# mag_encoder_Rev1.net
KiCad netlist of a schematic drawn in EAGLE
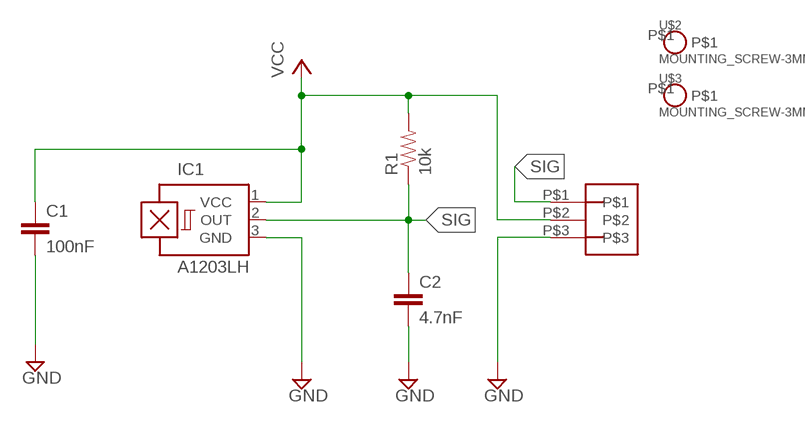
[diagram p0: schematic, sheet 1]

(export (version "E")
  (design (tool "Eeschema 10.0.6"))
  (components
    (comp (ref "C1")
      (value "100nF")
      (footprint "eagle-import:0603-CAP")
      (libsource (lib "eagle-import") (part "CAP0603-CAP"))
    )
    (comp (ref "C2")
      (value "4.7nF")
      (footprint "eagle-import:0603-CAP")
      (libsource (lib "eagle-import") (part "4.7NF-50V-10%(0603)"))
    )
    (comp (ref "IC1")
      (value "A1203LH")
      (footprint "eagle-import:SOT23-W")
      (fields (field (name "MF") "ALLEGRO MICROSYSTEMS, INC.") (field (name "MPN") "A1203LLHLT-T"))
      (libsource (lib "eagle-import") (part "A12?LH03"))
    )
    (comp (ref "R1")
      (value "10k")
      (footprint "eagle-import:0603")
      (libsource (lib "eagle-import") (part "10.5KOHM1/10W1%(0603)"))
    )
    (comp (ref "U$1")
      (value "3_PIN_JST-XH")
      (footprint "eagle-import:3_PIN_JST-XH")
      (libsource (lib "eagle-import") (part "3_PIN_JST-XH"))
    )
    (comp (ref "U$2")
      (value "MOUNTING_SCREW-3MM")
      (footprint "eagle-import:MOUNTING_SCREW-3MM")
      (libsource (lib "eagle-import") (part "MOUNTING_SCREW-3MM"))
    )
    (comp (ref "U$3")
      (value "MOUNTING_SCREW-3MM")
      (footprint "eagle-import:MOUNTING_SCREW-3MM")
      (libsource (lib "eagle-import") (part "MOUNTING_SCREW-3MM"))
    )
  )
  (nets
    (net (code "1") (name "GND") (class "Default")
      (node (ref "C1") (pin "2") (pinfunction "2_2") (pintype "passive"))
      (node (ref "C2") (pin "2") (pinfunction "2_2") (pintype "passive"))
      (node (ref "IC1") (pin "3") (pinfunction "GND_3") (pintype "power_in"))
      (node (ref "U$1") (pin "P$3") (pinfunction "P$3_P$3") (pintype "bidirectional"))
    )
    (net (code "2") (name "SIG") (class "Default")
      (node (ref "C2") (pin "1") (pinfunction "1_1") (pintype "passive"))
      (node (ref "IC1") (pin "2") (pinfunction "OUT_2") (pintype "output"))
      (node (ref "R1") (pin "1") (pinfunction "1_1") (pintype "passive"))
      (node (ref "U$1") (pin "P$1") (pinfunction "P$1_P$1") (pintype "bidirectional"))
    )
    (net (code "3") (name "VCC") (class "Default")
      (node (ref "C1") (pin "1") (pinfunction "1_1") (pintype "passive"))
      (node (ref "IC1") (pin "1") (pinfunction "VCC_1") (pintype "power_in"))
      (node (ref "R1") (pin "2") (pinfunction "2_2") (pintype "passive"))
      (node (ref "U$1") (pin "P$2") (pinfunction "P$2_P$2") (pintype "bidirectional"))
    )
    (net (code "4") (name "unconnected-(U$2-PadP$1)") (class "Default")
      (node (ref "U$2") (pin "P$1") (pinfunction "P$1_P$1") (pintype "bidirectional"))
    )
    (net (code "5") (name "unconnected-(U$3-PadP$1)") (class "Default")
      (node (ref "U$3") (pin "P$1") (pinfunction "P$1_P$1") (pintype "bidirectional"))
    )
  )
)
